# Robberto.net
KiCad netlist of a schematic drawn in EAGLE
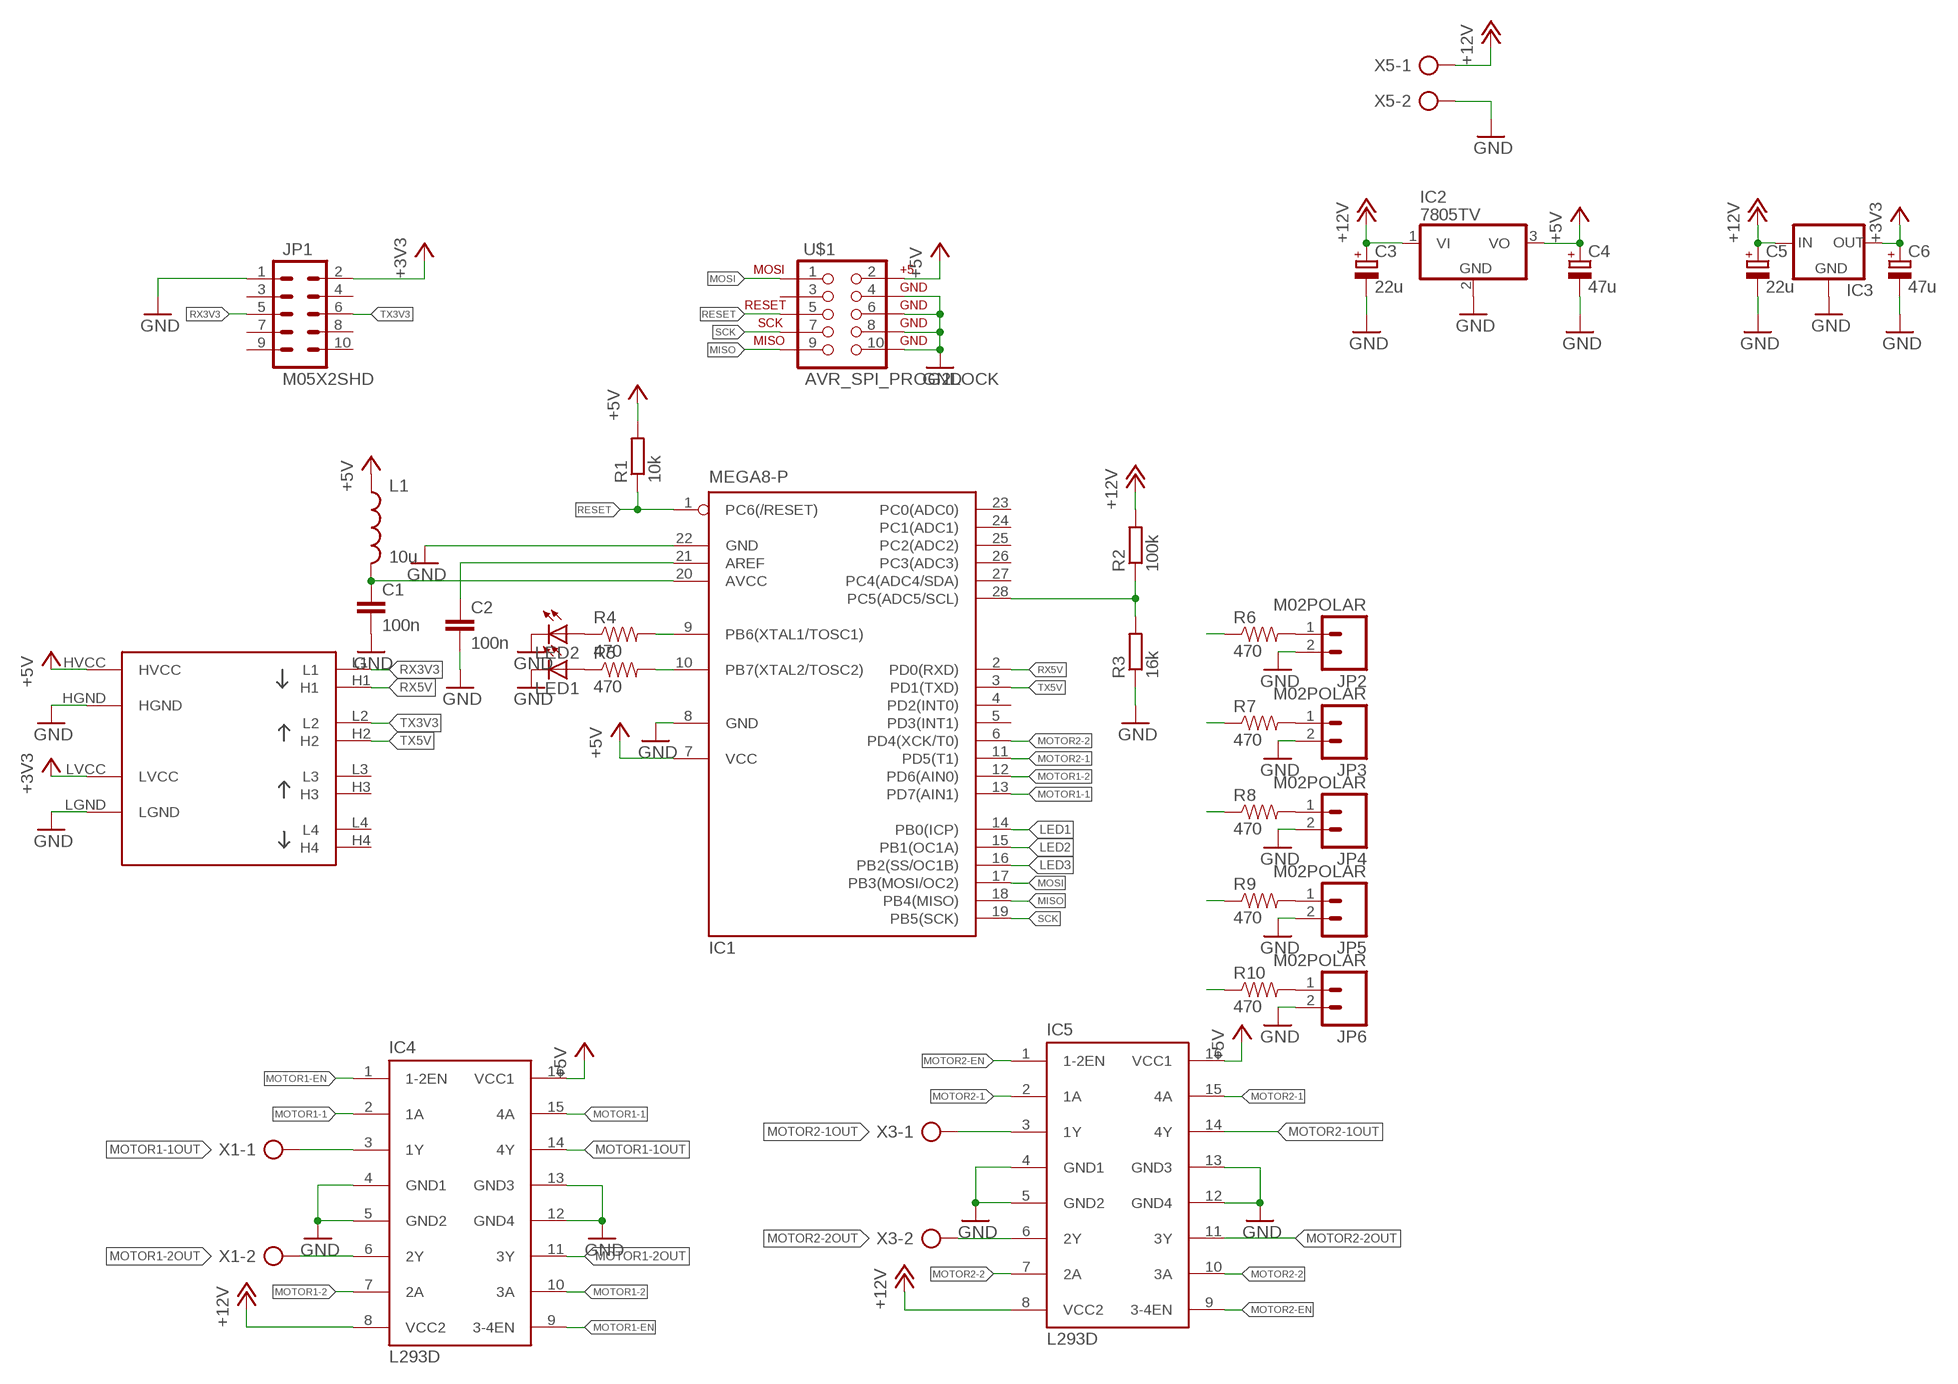
[diagram p0: schematic, sheet 1]

(export (version "E")
  (design (tool "Eeschema 10.0.6"))
  (components
    (comp (ref "C1")
      (value "100n")
      (footprint "eagle-import:C0805")
      (libsource (lib "eagle-import") (part "C-EUC0805"))
    )
    (comp (ref "C2")
      (value "100n")
      (footprint "eagle-import:C0805")
      (libsource (lib "eagle-import") (part "C-EUC0805"))
    )
    (comp (ref "C3")
      (value "22u")
      (footprint "eagle-import:E2,5-7")
      (libsource (lib "eagle-import") (part "CPOL-EUE2.5-7"))
    )
    (comp (ref "C4")
      (value "47u")
      (footprint "eagle-import:E2,5-7")
      (libsource (lib "eagle-import") (part "CPOL-EUE2.5-7"))
    )
    (comp (ref "C5")
      (value "22u")
      (footprint "eagle-import:E2,5-7")
      (libsource (lib "eagle-import") (part "CPOL-EUE2.5-7"))
    )
    (comp (ref "C6")
      (value "47u")
      (footprint "eagle-import:E2,5-7")
      (libsource (lib "eagle-import") (part "CPOL-EUE2.5-7"))
    )
    (comp (ref "IC1")
      (value "MEGA8-P")
      (footprint "eagle-import:DIL28-3")
      (libsource (lib "eagle-import") (part "MEGA8-P"))
    )
    (comp (ref "IC2")
      (value "7805TV")
      (footprint "eagle-import:TO220V")
      (libsource (lib "eagle-import") (part "78TV05"))
    )
    (comp (ref "IC3")
      (value "LFXXCVS")
      (footprint "eagle-import:TO220S")
      (libsource (lib "eagle-import") (part "LFXXCVS"))
    )
    (comp (ref "IC4")
      (value "L293D")
      (footprint "eagle-import:DIL16")
      (libsource (lib "eagle-import") (part "L293D"))
    )
    (comp (ref "IC5")
      (value "L293D")
      (footprint "eagle-import:DIL16")
      (libsource (lib "eagle-import") (part "L293D"))
    )
    (comp (ref "JP1")
      (value "M05X2SHD")
      (footprint "eagle-import:2X5-SHROUDED")
      (libsource (lib "eagle-import") (part "M05X2SHD"))
    )
    (comp (ref "JP2")
      (value "M02POLAR")
      (footprint "eagle-import:MOLEX-1X2")
      (libsource (lib "eagle-import") (part "M02POLAR"))
    )
    (comp (ref "JP3")
      (value "M02POLAR")
      (footprint "eagle-import:MOLEX-1X2")
      (libsource (lib "eagle-import") (part "M02POLAR"))
    )
    (comp (ref "JP4")
      (value "M02POLAR")
      (footprint "eagle-import:MOLEX-1X2")
      (libsource (lib "eagle-import") (part "M02POLAR"))
    )
    (comp (ref "JP5")
      (value "M02POLAR")
      (footprint "eagle-import:MOLEX-1X2")
      (libsource (lib "eagle-import") (part "M02POLAR"))
    )
    (comp (ref "JP6")
      (value "M02POLAR")
      (footprint "eagle-import:MOLEX-1X2")
      (libsource (lib "eagle-import") (part "M02POLAR"))
    )
    (comp (ref "L1")
      (value "10u")
      (footprint "eagle-import:0805")
      (libsource (lib "eagle-import") (part "INDUCTOR0805"))
    )
    (comp (ref "LED1")
      (value "LEDSML0805")
      (footprint "eagle-import:SML0805")
      (libsource (lib "eagle-import") (part "LEDSML0805"))
    )
    (comp (ref "LED2")
      (value "LEDSML0805")
      (footprint "eagle-import:SML0805")
      (libsource (lib "eagle-import") (part "LEDSML0805"))
    )
    (comp (ref "R1")
      (value "10k")
      (footprint "eagle-import:M0805")
      (libsource (lib "eagle-import") (part "R-EU_M0805"))
    )
    (comp (ref "R2")
      (value "100k")
      (footprint "eagle-import:M0805")
      (libsource (lib "eagle-import") (part "R-EU_M0805"))
    )
    (comp (ref "R3")
      (value "16k")
      (footprint "eagle-import:M0805")
      (libsource (lib "eagle-import") (part "R-EU_M0805"))
    )
    (comp (ref "R4")
      (value "470")
      (footprint "eagle-import:0805")
      (libsource (lib "eagle-import") (part "RESISTOR0805-RES"))
    )
    (comp (ref "R5")
      (value "470")
      (footprint "eagle-import:0805")
      (libsource (lib "eagle-import") (part "RESISTOR0805-RES"))
    )
    (comp (ref "R6")
      (value "470")
      (footprint "eagle-import:0805")
      (libsource (lib "eagle-import") (part "RESISTOR0805-RES"))
    )
    (comp (ref "R7")
      (value "470")
      (footprint "eagle-import:0805")
      (libsource (lib "eagle-import") (part "RESISTOR0805-RES"))
    )
    (comp (ref "R8")
      (value "470")
      (footprint "eagle-import:0805")
      (libsource (lib "eagle-import") (part "RESISTOR0805-RES"))
    )
    (comp (ref "R9")
      (value "470")
      (footprint "eagle-import:0805")
      (libsource (lib "eagle-import") (part "RESISTOR0805-RES"))
    )
    (comp (ref "R10")
      (value "470")
      (footprint "eagle-import:0805")
      (libsource (lib "eagle-import") (part "RESISTOR0805-RES"))
    )
    (comp (ref "U$1")
      (value "AVR_SPI_PROG2LOCK")
      (footprint "eagle-import:2X5-SHROUDED_LOCK")
      (libsource (lib "eagle-import") (part "AVR_SPI_PROG2LOCK"))
    )
    (comp (ref "U$2")
      (value "ELECTROPARK")
      (footprint "eagle-import:ELECTROPARK")
      (libsource (lib "eagle-import") (part "ELECTROPARK"))
    )
    (comp (ref "X1")
      (value "AK300/2")
      (footprint "eagle-import:AK300_2")
      (libsource (lib "eagle-import") (part "AK300/2"))
    )
    (comp (ref "X3")
      (value "AK300/2")
      (footprint "eagle-import:AK300_2")
      (libsource (lib "eagle-import") (part "AK300/2"))
    )
    (comp (ref "X5")
      (value "AK300/2")
      (footprint "eagle-import:AK300_2")
      (libsource (lib "eagle-import") (part "AK300/2"))
    )
  )
  (nets
    (net (code "1") (name "+3V3") (class "Default")
      (node (ref "C6") (pin "+") (pinfunction "+_+") (pintype "passive"))
      (node (ref "IC3") (pin "3") (pinfunction "OUT_3") (pintype "passive"))
      (node (ref "JP1") (pin "2") (pinfunction "2_2") (pintype "passive"))
      (node (ref "U$2") (pin "LVCC") (pinfunction "LVCC_LVCC") (pintype "bidirectional"))
    )
    (net (code "2") (name "+5V") (class "Default")
      (node (ref "C4") (pin "+") (pinfunction "+_+") (pintype "passive"))
      (node (ref "IC1") (pin "7") (pinfunction "VCC_7") (pintype "power_in"))
      (node (ref "IC2") (pin "3") (pinfunction "VO_3") (pintype "passive"))
      (node (ref "IC4") (pin "16") (pinfunction "VCC1_16") (pintype "power_in"))
      (node (ref "IC5") (pin "16") (pinfunction "VCC1_16") (pintype "power_in"))
      (node (ref "L1") (pin "1") (pinfunction "1_1") (pintype "passive"))
      (node (ref "R1") (pin "2") (pinfunction "2_2") (pintype "passive"))
      (node (ref "U$1") (pin "2") (pinfunction "2_2") (pintype "passive"))
      (node (ref "U$2") (pin "HVCC") (pinfunction "HVCC_HVCC") (pintype "bidirectional"))
    )
    (net (code "3") (name "+12V") (class "Default")
      (node (ref "C3") (pin "+") (pinfunction "+_+") (pintype "passive"))
      (node (ref "C5") (pin "+") (pinfunction "+_+") (pintype "passive"))
      (node (ref "IC2") (pin "1") (pinfunction "VI_1") (pintype "input"))
      (node (ref "IC3") (pin "1") (pinfunction "IN_1") (pintype "input"))
      (node (ref "IC4") (pin "8") (pinfunction "VCC2_8") (pintype "power_in"))
      (node (ref "IC5") (pin "8") (pinfunction "VCC2_8") (pintype "power_in"))
      (node (ref "R2") (pin "2") (pinfunction "2_2") (pintype "passive"))
      (node (ref "X5") (pin "1") (pinfunction "KL_1") (pintype "passive"))
    )
    (net (code "4") (name "GND") (class "Default")
      (node (ref "C1") (pin "2") (pinfunction "2_2") (pintype "passive"))
      (node (ref "C2") (pin "2") (pinfunction "2_2") (pintype "passive"))
      (node (ref "C3") (pin "-") (pinfunction "-_-") (pintype "passive"))
      (node (ref "C4") (pin "-") (pinfunction "-_-") (pintype "passive"))
      (node (ref "C5") (pin "-") (pinfunction "-_-") (pintype "passive"))
      (node (ref "C6") (pin "-") (pinfunction "-_-") (pintype "passive"))
      (node (ref "IC1") (pin "22") (pinfunction "GND_22") (pintype "power_in"))
      (node (ref "IC1") (pin "8") (pinfunction "GND_8") (pintype "power_in"))
      (node (ref "IC2") (pin "2") (pinfunction "GND_2") (pintype "passive"))
      (node (ref "IC3") (pin "2") (pinfunction "GND_2") (pintype "input"))
      (node (ref "IC4") (pin "12") (pinfunction "GND4_12") (pintype "power_in"))
      (node (ref "IC4") (pin "13") (pinfunction "GND3_13") (pintype "power_in"))
      (node (ref "IC4") (pin "4") (pinfunction "GND1_4") (pintype "power_in"))
      (node (ref "IC4") (pin "5") (pinfunction "GND2_5") (pintype "power_in"))
      (node (ref "IC5") (pin "12") (pinfunction "GND4_12") (pintype "power_in"))
      (node (ref "IC5") (pin "13") (pinfunction "GND3_13") (pintype "power_in"))
      (node (ref "IC5") (pin "4") (pinfunction "GND1_4") (pintype "power_in"))
      (node (ref "IC5") (pin "5") (pinfunction "GND2_5") (pintype "power_in"))
      (node (ref "JP1") (pin "1") (pinfunction "1_1") (pintype "passive"))
      (node (ref "JP2") (pin "2") (pinfunction "2_2") (pintype "passive"))
      (node (ref "JP3") (pin "2") (pinfunction "2_2") (pintype "passive"))
      (node (ref "JP4") (pin "2") (pinfunction "2_2") (pintype "passive"))
      (node (ref "JP5") (pin "2") (pinfunction "2_2") (pintype "passive"))
      (node (ref "JP6") (pin "2") (pinfunction "2_2") (pintype "passive"))
      (node (ref "LED1") (pin "C") (pinfunction "C_C") (pintype "passive"))
      (node (ref "LED2") (pin "C") (pinfunction "C_C") (pintype "passive"))
      (node (ref "R3") (pin "1") (pinfunction "1_1") (pintype "passive"))
      (node (ref "U$1") (pin "10") (pinfunction "10_10") (pintype "passive"))
      (node (ref "U$1") (pin "4") (pinfunction "4_4") (pintype "passive"))
      (node (ref "U$1") (pin "6") (pinfunction "6_6") (pintype "passive"))
      (node (ref "U$1") (pin "8") (pinfunction "8_8") (pintype "passive"))
      (node (ref "U$2") (pin "HGND") (pinfunction "HGND_HGND") (pintype "bidirectional"))
      (node (ref "U$2") (pin "LGND") (pinfunction "LGND_LGND") (pintype "bidirectional"))
      (node (ref "X5") (pin "2") (pinfunction "KL_2") (pintype "passive"))
    )
    (net (code "5") (name "LED1") (class "Default")
      (node (ref "IC1") (pin "14") (pinfunction "PB0(ICP)_14") (pintype "bidirectional"))
      (node (ref "R6") (pin "1") (pinfunction "1_1") (pintype "passive"))
    )
    (net (code "6") (name "LED2") (class "Default")
      (node (ref "IC1") (pin "15") (pinfunction "PB1(OC1A)_15") (pintype "bidirectional"))
      (node (ref "R7") (pin "1") (pinfunction "1_1") (pintype "passive"))
    )
    (net (code "7") (name "LED3") (class "Default")
      (node (ref "IC1") (pin "16") (pinfunction "PB2(SS/OC1B)_16") (pintype "bidirectional"))
      (node (ref "R8") (pin "1") (pinfunction "1_1") (pintype "passive"))
    )
    (net (code "8") (name "MISO") (class "Default")
      (node (ref "IC1") (pin "18") (pinfunction "PB4(MISO)_18") (pintype "bidirectional"))
      (node (ref "R10") (pin "1") (pinfunction "1_1") (pintype "passive"))
      (node (ref "U$1") (pin "9") (pinfunction "9_9") (pintype "passive"))
    )
    (net (code "9") (name "MOSI") (class "Default")
      (node (ref "IC1") (pin "17") (pinfunction "PB3(MOSI/OC2)_17") (pintype "bidirectional"))
      (node (ref "R9") (pin "1") (pinfunction "1_1") (pintype "passive"))
      (node (ref "U$1") (pin "1") (pinfunction "1_1") (pintype "passive"))
    )
    (net (code "10") (name "MOTOR1-1") (class "Default")
      (node (ref "IC1") (pin "13") (pinfunction "PD7(AIN1)_13") (pintype "bidirectional"))
      (node (ref "IC4") (pin "15") (pinfunction "4A_15") (pintype "input"))
      (node (ref "IC4") (pin "2") (pinfunction "1A_2") (pintype "input"))
    )
    (net (code "11") (name "MOTOR1-1OUT") (class "Default")
      (node (ref "IC4") (pin "14") (pinfunction "4Y_14") (pintype "output"))
      (node (ref "IC4") (pin "3") (pinfunction "1Y_3") (pintype "output"))
      (node (ref "X1") (pin "1") (pinfunction "KL_1") (pintype "passive"))
    )
    (net (code "12") (name "MOTOR1-2") (class "Default")
      (node (ref "IC1") (pin "12") (pinfunction "PD6(AIN0)_12") (pintype "bidirectional"))
      (node (ref "IC4") (pin "10") (pinfunction "3A_10") (pintype "input"))
      (node (ref "IC4") (pin "7") (pinfunction "2A_7") (pintype "input"))
    )
    (net (code "13") (name "MOTOR1-2OUT") (class "Default")
      (node (ref "IC4") (pin "11") (pinfunction "3Y_11") (pintype "output"))
      (node (ref "IC4") (pin "6") (pinfunction "2Y_6") (pintype "output"))
      (node (ref "X1") (pin "2") (pinfunction "KL_2") (pintype "passive"))
    )
    (net (code "14") (name "MOTOR1-EN") (class "Default")
      (node (ref "IC4") (pin "1") (pinfunction "1-2EN_1") (pintype "input"))
      (node (ref "IC4") (pin "9") (pinfunction "3-4EN_9") (pintype "input"))
    )
    (net (code "15") (name "MOTOR2-1") (class "Default")
      (node (ref "IC1") (pin "11") (pinfunction "PD5(T1)_11") (pintype "bidirectional"))
      (node (ref "IC5") (pin "15") (pinfunction "4A_15") (pintype "input"))
      (node (ref "IC5") (pin "2") (pinfunction "1A_2") (pintype "input"))
    )
    (net (code "16") (name "MOTOR2-1OUT") (class "Default")
      (node (ref "IC5") (pin "14") (pinfunction "4Y_14") (pintype "output"))
      (node (ref "IC5") (pin "3") (pinfunction "1Y_3") (pintype "output"))
      (node (ref "X3") (pin "1") (pinfunction "KL_1") (pintype "passive"))
    )
    (net (code "17") (name "MOTOR2-2") (class "Default")
      (node (ref "IC1") (pin "6") (pinfunction "PD4(XCK/T0)_6") (pintype "bidirectional"))
      (node (ref "IC5") (pin "10") (pinfunction "3A_10") (pintype "input"))
      (node (ref "IC5") (pin "7") (pinfunction "2A_7") (pintype "input"))
    )
    (net (code "18") (name "MOTOR2-2OUT") (class "Default")
      (node (ref "IC5") (pin "11") (pinfunction "3Y_11") (pintype "output"))
      (node (ref "IC5") (pin "6") (pinfunction "2Y_6") (pintype "output"))
      (node (ref "X3") (pin "2") (pinfunction "KL_2") (pintype "passive"))
    )
    (net (code "19") (name "MOTOR2-EN") (class "Default")
      (node (ref "IC5") (pin "1") (pinfunction "1-2EN_1") (pintype "input"))
      (node (ref "IC5") (pin "9") (pinfunction "3-4EN_9") (pintype "input"))
    )
    (net (code "20") (name "Net-(IC1-AREF)") (class "Default")
      (node (ref "C2") (pin "1") (pinfunction "1_1") (pintype "passive"))
      (node (ref "IC1") (pin "21") (pinfunction "AREF_21") (pintype "passive"))
    )
    (net (code "21") (name "Net-(IC1-AVCC)") (class "Default")
      (node (ref "C1") (pin "1") (pinfunction "1_1") (pintype "passive"))
      (node (ref "IC1") (pin "20") (pinfunction "AVCC_20") (pintype "power_in"))
      (node (ref "L1") (pin "2") (pinfunction "2_2") (pintype "passive"))
    )
    (net (code "22") (name "Net-(IC1-PB6(XTAL1{slash}TOSC1))") (class "Default")
      (node (ref "IC1") (pin "9") (pinfunction "PB6(XTAL1/TOSC1)_9") (pintype "bidirectional"))
      (node (ref "R4") (pin "2") (pinfunction "2_2") (pintype "passive"))
    )
    (net (code "23") (name "Net-(IC1-PB7(XTAL2{slash}TOSC2))") (class "Default")
      (node (ref "IC1") (pin "10") (pinfunction "PB7(XTAL2/TOSC2)_10") (pintype "bidirectional"))
      (node (ref "R5") (pin "2") (pinfunction "2_2") (pintype "passive"))
    )
    (net (code "24") (name "Net-(IC1-PC5(ADC5{slash}SCL))") (class "Default")
      (node (ref "IC1") (pin "28") (pinfunction "PC5(ADC5/SCL)_28") (pintype "bidirectional"))
      (node (ref "R2") (pin "1") (pinfunction "1_1") (pintype "passive"))
      (node (ref "R3") (pin "2") (pinfunction "2_2") (pintype "passive"))
    )
    (net (code "25") (name "Net-(JP2-Pad1)") (class "Default")
      (node (ref "JP2") (pin "1") (pinfunction "1_1") (pintype "passive"))
      (node (ref "R6") (pin "2") (pinfunction "2_2") (pintype "passive"))
    )
    (net (code "26") (name "Net-(JP3-Pad1)") (class "Default")
      (node (ref "JP3") (pin "1") (pinfunction "1_1") (pintype "passive"))
      (node (ref "R7") (pin "2") (pinfunction "2_2") (pintype "passive"))
    )
    (net (code "27") (name "Net-(JP4-Pad1)") (class "Default")
      (node (ref "JP4") (pin "1") (pinfunction "1_1") (pintype "passive"))
      (node (ref "R8") (pin "2") (pinfunction "2_2") (pintype "passive"))
    )
    (net (code "28") (name "Net-(JP5-Pad1)") (class "Default")
      (node (ref "JP5") (pin "1") (pinfunction "1_1") (pintype "passive"))
      (node (ref "R9") (pin "2") (pinfunction "2_2") (pintype "passive"))
    )
    (net (code "29") (name "Net-(JP6-Pad1)") (class "Default")
      (node (ref "JP6") (pin "1") (pinfunction "1_1") (pintype "passive"))
      (node (ref "R10") (pin "2") (pinfunction "2_2") (pintype "passive"))
    )
    (net (code "30") (name "Net-(LED1-PadA)") (class "Default")
      (node (ref "LED1") (pin "A") (pinfunction "A_A") (pintype "passive"))
      (node (ref "R5") (pin "1") (pinfunction "1_1") (pintype "passive"))
    )
    (net (code "31") (name "Net-(LED2-PadA)") (class "Default")
      (node (ref "LED2") (pin "A") (pinfunction "A_A") (pintype "passive"))
      (node (ref "R4") (pin "1") (pinfunction "1_1") (pintype "passive"))
    )
    (net (code "32") (name "RESET") (class "Default")
      (node (ref "IC1") (pin "1") (pinfunction "PC6(/RESET)_1") (pintype "bidirectional"))
      (node (ref "R1") (pin "1") (pinfunction "1_1") (pintype "passive"))
      (node (ref "U$1") (pin "5") (pinfunction "5_5") (pintype "passive"))
    )
    (net (code "33") (name "RX3V3") (class "Default")
      (node (ref "JP1") (pin "5") (pinfunction "5_5") (pintype "passive"))
      (node (ref "U$2") (pin "L1") (pinfunction "L1_L1") (pintype "bidirectional"))
    )
    (net (code "34") (name "RX5V") (class "Default")
      (node (ref "IC1") (pin "2") (pinfunction "PD0(RXD)_2") (pintype "bidirectional"))
      (node (ref "U$2") (pin "H1") (pinfunction "H1_H1") (pintype "bidirectional"))
    )
    (net (code "35") (name "SCK") (class "Default")
      (node (ref "IC1") (pin "19") (pinfunction "PB5(SCK)_19") (pintype "bidirectional"))
      (node (ref "U$1") (pin "7") (pinfunction "7_7") (pintype "passive"))
    )
    (net (code "36") (name "TX3V3") (class "Default")
      (node (ref "JP1") (pin "6") (pinfunction "6_6") (pintype "passive"))
      (node (ref "U$2") (pin "L2") (pinfunction "L2_L2") (pintype "bidirectional"))
    )
    (net (code "37") (name "TX5V") (class "Default")
      (node (ref "IC1") (pin "3") (pinfunction "PD1(TXD)_3") (pintype "bidirectional"))
      (node (ref "U$2") (pin "H2") (pinfunction "H2_H2") (pintype "bidirectional"))
    )
    (net (code "38") (name "unconnected-(IC1-PC0(ADC0)-Pad23)") (class "Default")
      (node (ref "IC1") (pin "23") (pinfunction "PC0(ADC0)_23") (pintype "bidirectional"))
    )
    (net (code "39") (name "unconnected-(IC1-PC1(ADC1)-Pad24)") (class "Default")
      (node (ref "IC1") (pin "24") (pinfunction "PC1(ADC1)_24") (pintype "bidirectional"))
    )
    (net (code "40") (name "unconnected-(IC1-PC2(ADC2)-Pad25)") (class "Default")
      (node (ref "IC1") (pin "25") (pinfunction "PC2(ADC2)_25") (pintype "bidirectional"))
    )
    (net (code "41") (name "unconnected-(IC1-PC3(ADC3)-Pad26)") (class "Default")
      (node (ref "IC1") (pin "26") (pinfunction "PC3(ADC3)_26") (pintype "bidirectional"))
    )
    (net (code "42") (name "unconnected-(IC1-PC4(ADC4{slash}SDA)-Pad27)") (class "Default")
      (node (ref "IC1") (pin "27") (pinfunction "PC4(ADC4/SDA)_27") (pintype "bidirectional"))
    )
    (net (code "43") (name "unconnected-(IC1-PD2(INT0)-Pad4)") (class "Default")
      (node (ref "IC1") (pin "4") (pinfunction "PD2(INT0)_4") (pintype "bidirectional"))
    )
    (net (code "44") (name "unconnected-(IC1-PD3(INT1)-Pad5)") (class "Default")
      (node (ref "IC1") (pin "5") (pinfunction "PD3(INT1)_5") (pintype "bidirectional"))
    )
    (net (code "45") (name "unconnected-(JP1-Pad3)") (class "Default")
      (node (ref "JP1") (pin "3") (pinfunction "3_3") (pintype "passive"))
    )
    (net (code "46") (name "unconnected-(JP1-Pad4)") (class "Default")
      (node (ref "JP1") (pin "4") (pinfunction "4_4") (pintype "passive"))
    )
    (net (code "47") (name "unconnected-(JP1-Pad7)") (class "Default")
      (node (ref "JP1") (pin "7") (pinfunction "7_7") (pintype "passive"))
    )
    (net (code "48") (name "unconnected-(JP1-Pad8)") (class "Default")
      (node (ref "JP1") (pin "8") (pinfunction "8_8") (pintype "passive"))
    )
    (net (code "49") (name "unconnected-(JP1-Pad9)") (class "Default")
      (node (ref "JP1") (pin "9") (pinfunction "9_9") (pintype "passive"))
    )
    (net (code "50") (name "unconnected-(JP1-Pad10)") (class "Default")
      (node (ref "JP1") (pin "10") (pinfunction "10_10") (pintype "passive"))
    )
    (net (code "51") (name "unconnected-(U$1-Pad3)") (class "Default")
      (node (ref "U$1") (pin "3") (pinfunction "3_3") (pintype "passive"))
    )
    (net (code "52") (name "unconnected-(U$2-PadH3)") (class "Default")
      (node (ref "U$2") (pin "H3") (pinfunction "H3_H3") (pintype "bidirectional"))
    )
    (net (code "53") (name "unconnected-(U$2-PadH4)") (class "Default")
      (node (ref "U$2") (pin "H4") (pinfunction "H4_H4") (pintype "bidirectional"))
    )
    (net (code "54") (name "unconnected-(U$2-PadL3)") (class "Default")
      (node (ref "U$2") (pin "L3") (pinfunction "L3_L3") (pintype "bidirectional"))
    )
    (net (code "55") (name "unconnected-(U$2-PadL4)") (class "Default")
      (node (ref "U$2") (pin "L4") (pinfunction "L4_L4") (pintype "bidirectional"))
    )
  )
)
